# MC50_Periph.net
KiCad netlist of a schematic drawn in Altium Designer
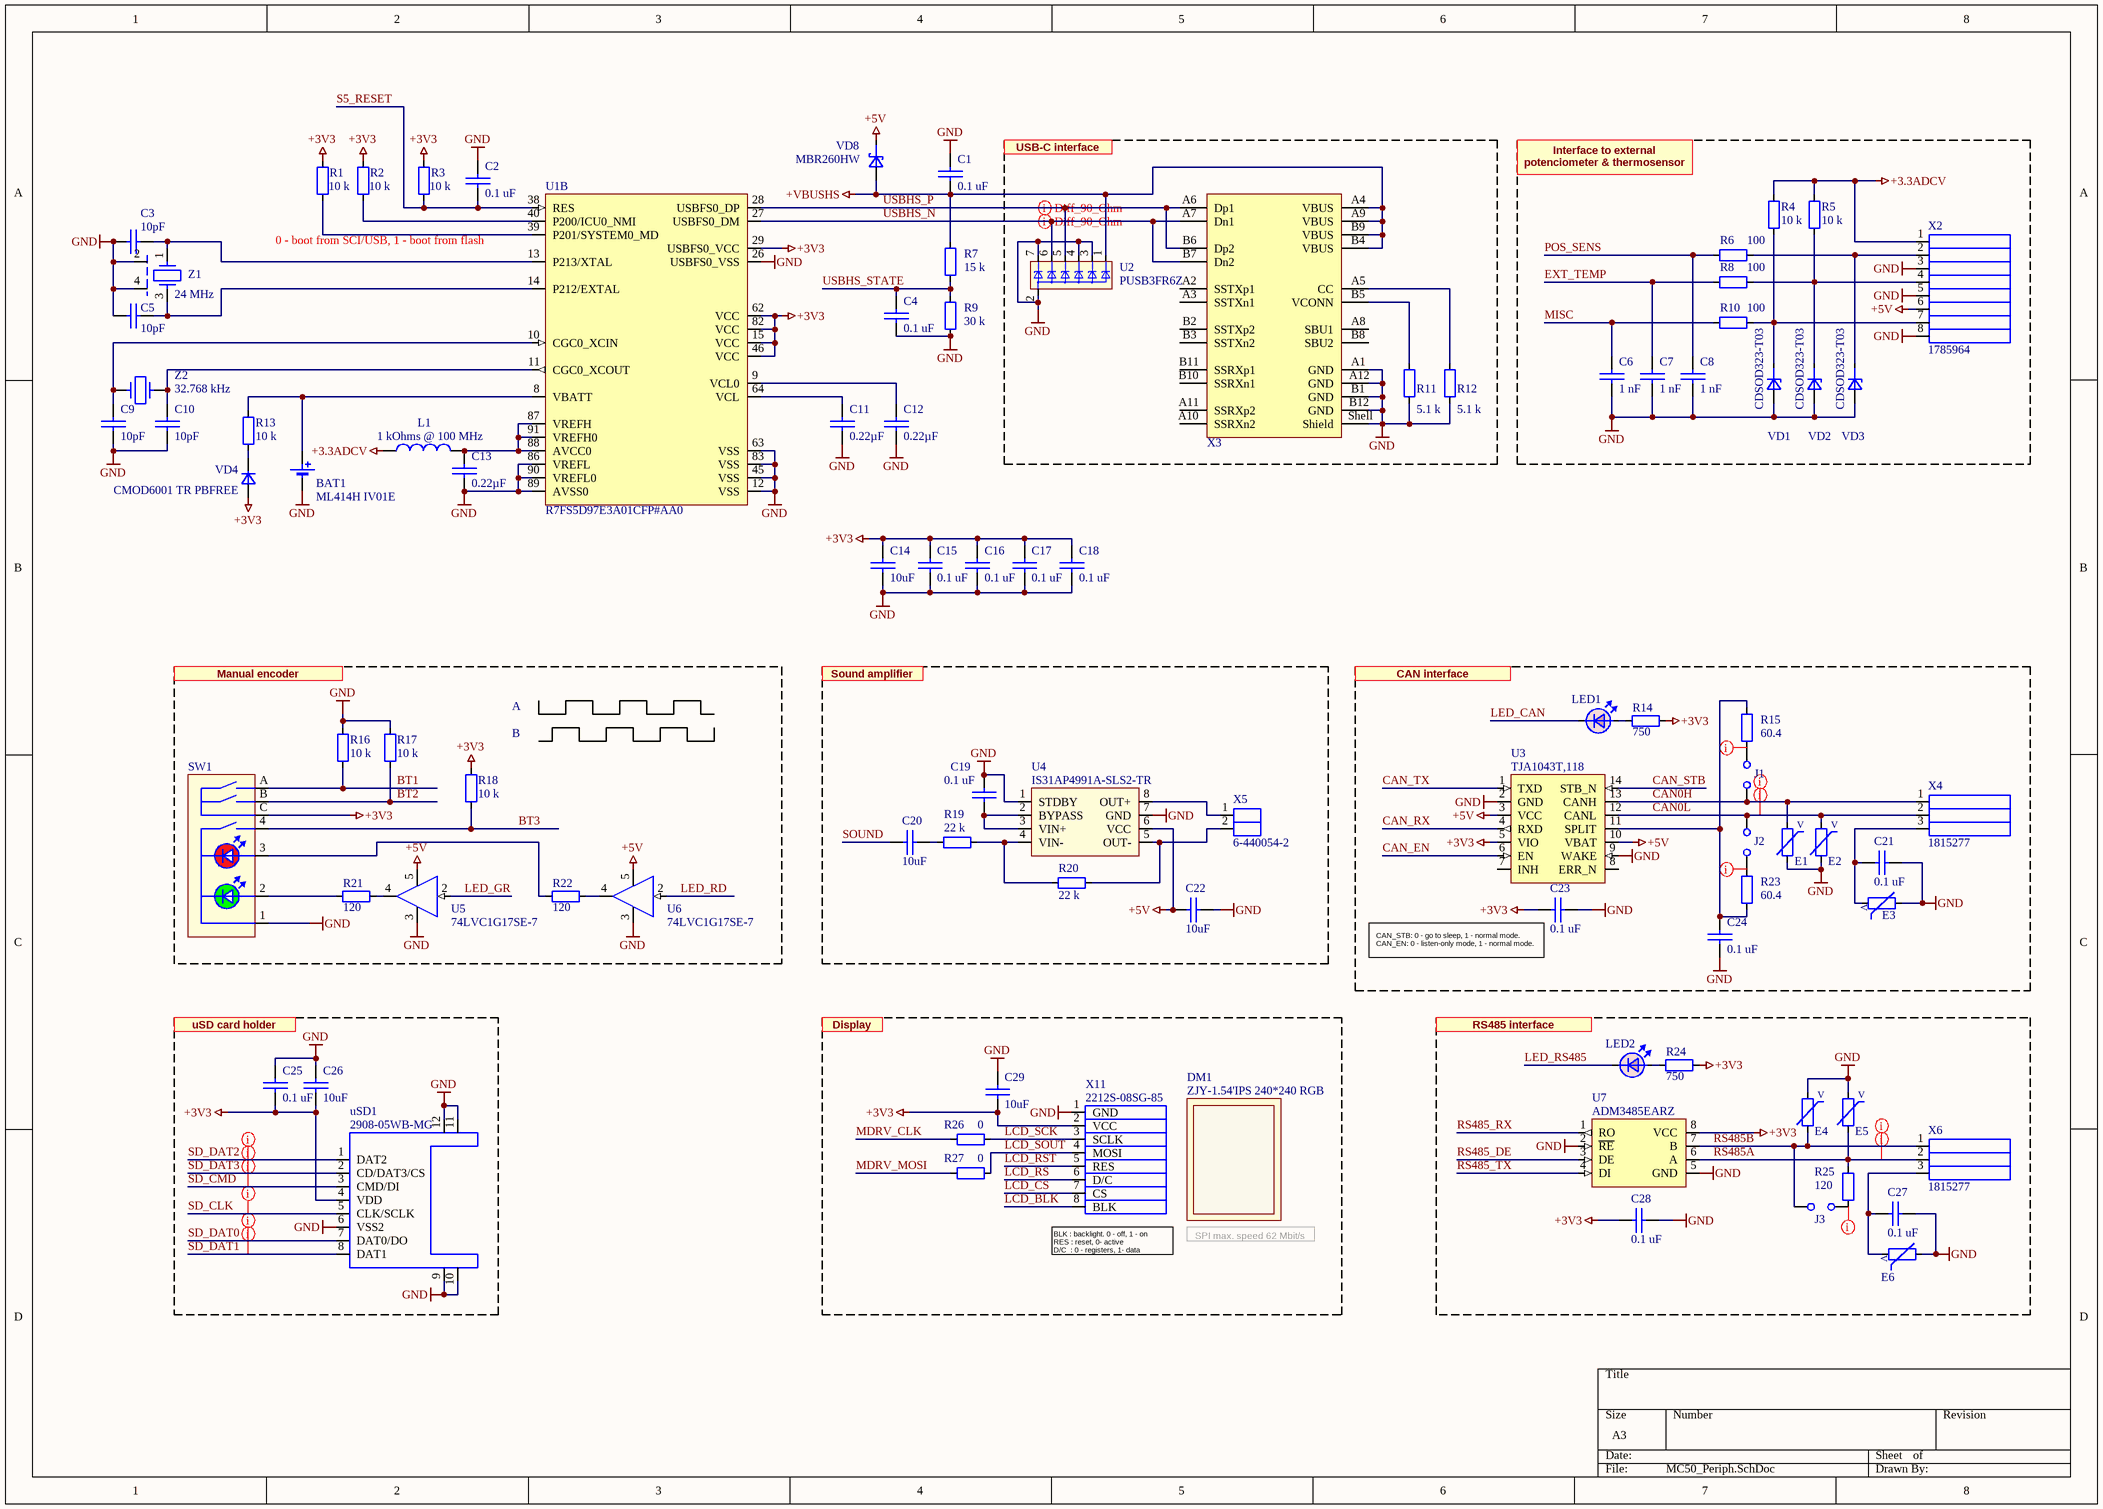
[diagram p0: MC50_Periph.SchDoc]

(export (version "E")
  (design (tool "Eeschema 10.0.6"))
  (components
    (comp (ref "BAT1")
      (value "ML414H IV01E")
      (footprint "ML414H")
      (description "Coin, 4.8mm 3V Lithium Battery Rechargeable (Secondary) 1mAh")
      (fields (field (name "PARTNUM") "728-1052-1-ND") (field (name "MANUFACTURER") "Seiko Instruments"))
      (libsource (lib "ea_PowerSources") (part "ML414H IV01E"))
    )
    (comp (ref "C1")
      (value "0.1 uF")
      (footprint "1608[0603]")
      (description "0.1 µF ±10% 50V Ceramic Capacitor X7R 0603 (1608 Metric),  \r\n-55°C ~ 125°C")
      (fields
        (field (name "TOLERANCE") "+-10%")
        (field (name "MANUFACTURER") "Walsin Technology Corporation")
      )
      (libsource (lib "ea_Capacitors_0603") (part "0603B104K500CT"))
    )
    (comp (ref "C2")
      (value "0.1 uF")
      (footprint "1608[0603]")
      (description "0.1 µF ±10% 50V Ceramic Capacitor X7R 0603 (1608 Metric),  \r\n-55°C ~ 125°C")
      (fields
        (field (name "TOLERANCE") "+-10%")
        (field (name "MANUFACTURER") "Walsin Technology Corporation")
      )
      (libsource (lib "ea_Capacitors_0603") (part "0603B104K500CT"))
    )
    (comp (ref "C3")
      (value "10pF")
      (footprint "0603 CAP")
      (description "10pF, ±5%, 50V, C0G, NP0, 0603 (1608 Metric), -55°C ~ 125°C, -, General Purpose")
      (fields
        (field (name "PART NUMBER") "CL10C100JB8NCNC")
        (field (name "MANUFACTURER") "Samsung Electro-Mechanics")
      )
      (libsource (lib "ea_PassivComps") (part "Capacitor"))
    )
    (comp (ref "C4")
      (value "0.1 uF")
      (footprint "1608[0603]")
      (description "0.1 µF ±10% 50V Ceramic Capacitor X7R 0603 (1608 Metric),  \r\n-55°C ~ 125°C")
      (fields
        (field (name "TOLERANCE") "+-10%")
        (field (name "MANUFACTURER") "Walsin Technology Corporation")
      )
      (libsource (lib "ea_Capacitors_0603") (part "0603B104K500CT"))
    )
    (comp (ref "C5")
      (value "10pF")
      (footprint "0603 CAP")
      (description "10pF, ±5%, 50V, C0G, NP0, 0603 (1608 Metric), -55°C ~ 125°C, -, General Purpose")
      (fields
        (field (name "PART NUMBER") "CL10C100JB8NCNC")
        (field (name "MANUFACTURER") "Samsung Electro-Mechanics")
      )
      (libsource (lib "ea_PassivComps") (part "Capacitor"))
    )
    (comp (ref "C6")
      (value "1 nF")
      (footprint "0603 CAP")
      (description "1000pF, ±5%, 50V, X7R, 0603 (1608 Metric), -55°C ~ 125°C, -, General Purpose")
      (fields (field (name "PART NUMBER") "CC0603JRX7R9BB102") (field (name "MANUFACTURER") "Yageo"))
      (libsource (lib "ea_PassivComps") (part "Capacitor"))
    )
    (comp (ref "C7")
      (value "1 nF")
      (footprint "0603 CAP")
      (description "1000pF, ±5%, 50V, X7R, 0603 (1608 Metric), -55°C ~ 125°C, -, General Purpose")
      (fields (field (name "PART NUMBER") "CC0603JRX7R9BB102") (field (name "MANUFACTURER") "Yageo"))
      (libsource (lib "ea_PassivComps") (part "Capacitor"))
    )
    (comp (ref "C8")
      (value "1 nF")
      (footprint "0603 CAP")
      (description "1000pF, ±5%, 50V, X7R, 0603 (1608 Metric), -55°C ~ 125°C, -, General Purpose")
      (fields (field (name "PART NUMBER") "CC0603JRX7R9BB102") (field (name "MANUFACTURER") "Yageo"))
      (libsource (lib "ea_PassivComps") (part "Capacitor"))
    )
    (comp (ref "C9")
      (value "10pF")
      (footprint "0603 CAP")
      (description "10pF, ±5%, 50V, C0G, NP0, 0603 (1608 Metric), -55°C ~ 125°C, -, General Purpose")
      (fields
        (field (name "PART NUMBER") "CL10C100JB8NCNC")
        (field (name "MANUFACTURER") "Samsung Electro-Mechanics")
      )
      (libsource (lib "ea_PassivComps") (part "Capacitor"))
    )
    (comp (ref "C10")
      (value "10pF")
      (footprint "0603 CAP")
      (description "10pF, ±5%, 50V, C0G, NP0, 0603 (1608 Metric), -55°C ~ 125°C, -, General Purpose")
      (fields
        (field (name "PART NUMBER") "CL10C100JB8NCNC")
        (field (name "MANUFACTURER") "Samsung Electro-Mechanics")
      )
      (libsource (lib "ea_PassivComps") (part "Capacitor"))
    )
    (comp (ref "C11")
      (value "0.22µF")
      (footprint "0603 CAP")
      (description "0.22µF, ±10%, 50V, X7R, 0603 (1608 Metric), -55°C ~ 125°C, -, General Purpose")
      (fields
        (field (name "PART NUMBER") "GRM188R71H224KAC4D")
        (field (name "MANUFACTURER") "Murata Electronics North America")
      )
      (libsource (lib "ea_PassivComps") (part "Capacitor"))
    )
    (comp (ref "C12")
      (value "0.22µF")
      (footprint "0603 CAP")
      (description "0.22µF, ±10%, 50V, X7R, 0603 (1608 Metric), -55°C ~ 125°C, -, General Purpose")
      (fields
        (field (name "PART NUMBER") "GRM188R71H224KAC4D")
        (field (name "MANUFACTURER") "Murata Electronics North America")
      )
      (libsource (lib "ea_PassivComps") (part "Capacitor"))
    )
    (comp (ref "C13")
      (value "0.22µF")
      (footprint "0603 CAP")
      (description "0.22µF, ±10%, 50V, X7R, 0603 (1608 Metric), -55°C ~ 125°C, -, General Purpose")
      (fields
        (field (name "PART NUMBER") "GRM188R71H224KAC4D")
        (field (name "MANUFACTURER") "Murata Electronics North America")
      )
      (libsource (lib "ea_PassivComps") (part "Capacitor"))
    )
    (comp (ref "C14")
      (value "10uF")
      (footprint "1608[0603]")
      (description "10 µF ±10% 25V Ceramic Capacitor X5R 0603 (1608 Metric), -55°C ~ 85°C")
      (fields (field (name "MANUFACTURER") "Murata Electronics") (field (name "TOLERANCE") "±10%"))
      (libsource (lib "ea_Capacitors_0603") (part "GRM188R61E106KA73D"))
    )
    (comp (ref "C15")
      (value "0.1 uF")
      (footprint "1608[0603]")
      (description "0.1 µF ±10% 50V Ceramic Capacitor X7R 0603 (1608 Metric),  \r\n-55°C ~ 125°C")
      (fields
        (field (name "TOLERANCE") "+-10%")
        (field (name "MANUFACTURER") "Walsin Technology Corporation")
      )
      (libsource (lib "ea_Capacitors_0603") (part "0603B104K500CT"))
    )
    (comp (ref "C16")
      (value "0.1 uF")
      (footprint "1608[0603]")
      (description "0.1 µF ±10% 50V Ceramic Capacitor X7R 0603 (1608 Metric),  \r\n-55°C ~ 125°C")
      (fields
        (field (name "TOLERANCE") "+-10%")
        (field (name "MANUFACTURER") "Walsin Technology Corporation")
      )
      (libsource (lib "ea_Capacitors_0603") (part "0603B104K500CT"))
    )
    (comp (ref "C17")
      (value "0.1 uF")
      (footprint "1608[0603]")
      (description "0.1 µF ±10% 50V Ceramic Capacitor X7R 0603 (1608 Metric),  \r\n-55°C ~ 125°C")
      (fields
        (field (name "TOLERANCE") "+-10%")
        (field (name "MANUFACTURER") "Walsin Technology Corporation")
      )
      (libsource (lib "ea_Capacitors_0603") (part "0603B104K500CT"))
    )
    (comp (ref "C18")
      (value "0.1 uF")
      (footprint "1608[0603]")
      (description "0.1 µF ±10% 50V Ceramic Capacitor X7R 0603 (1608 Metric),  \r\n-55°C ~ 125°C")
      (fields
        (field (name "TOLERANCE") "+-10%")
        (field (name "MANUFACTURER") "Walsin Technology Corporation")
      )
      (libsource (lib "ea_Capacitors_0603") (part "0603B104K500CT"))
    )
    (comp (ref "C19")
      (value "0.1 uF")
      (footprint "1608[0603]")
      (description "0.1 µF ±10% 50V Ceramic Capacitor X7R 0603 (1608 Metric),  \r\n-55°C ~ 125°C")
      (fields
        (field (name "TOLERANCE") "+-10%")
        (field (name "MANUFACTURER") "Walsin Technology Corporation")
      )
      (libsource (lib "ea_Capacitors_0603") (part "0603B104K500CT"))
    )
    (comp (ref "C20")
      (value "10uF")
      (footprint "1608[0603]")
      (description "10 µF ±10% 25V Ceramic Capacitor X5R 0603 (1608 Metric), -55°C ~ 85°C")
      (fields (field (name "MANUFACTURER") "Murata Electronics") (field (name "TOLERANCE") "±10%"))
      (libsource (lib "ea_Capacitors_0603") (part "GRM188R61E106KA73D"))
    )
    (comp (ref "C21")
      (value "0.1 uF")
      (footprint "1608[0603]")
      (description "0.1 µF ±10% 50V Ceramic Capacitor X7R 0603 (1608 Metric),  \r\n-55°C ~ 125°C")
      (fields
        (field (name "TOLERANCE") "+-10%")
        (field (name "MANUFACTURER") "Walsin Technology Corporation")
      )
      (libsource (lib "ea_Capacitors_0603") (part "0603B104K500CT"))
    )
    (comp (ref "C22")
      (value "10uF")
      (footprint "1608[0603]")
      (description "10 µF ±10% 25V Ceramic Capacitor X5R 0603 (1608 Metric), -55°C ~ 85°C")
      (fields (field (name "MANUFACTURER") "Murata Electronics") (field (name "TOLERANCE") "±10%"))
      (libsource (lib "ea_Capacitors_0603") (part "GRM188R61E106KA73D"))
    )
    (comp (ref "C23")
      (value "0.1 uF")
      (footprint "1608[0603]")
      (description "0.1 µF ±10% 50V Ceramic Capacitor X7R 0603 (1608 Metric),  \r\n-55°C ~ 125°C")
      (fields
        (field (name "TOLERANCE") "+-10%")
        (field (name "MANUFACTURER") "Walsin Technology Corporation")
      )
      (libsource (lib "ea_Capacitors_0603") (part "0603B104K500CT"))
    )
    (comp (ref "C24")
      (value "0.1 uF")
      (footprint "1608[0603]")
      (description "0.1 µF ±10% 50V Ceramic Capacitor X7R 0603 (1608 Metric),  \r\n-55°C ~ 125°C")
      (fields
        (field (name "TOLERANCE") "+-10%")
        (field (name "MANUFACTURER") "Walsin Technology Corporation")
      )
      (libsource (lib "ea_Capacitors_0603") (part "0603B104K500CT"))
    )
    (comp (ref "C25")
      (value "0.1 uF")
      (footprint "1608[0603]")
      (description "0.1 µF ±10% 50V Ceramic Capacitor X7R 0603 (1608 Metric),  \r\n-55°C ~ 125°C")
      (fields
        (field (name "TOLERANCE") "+-10%")
        (field (name "MANUFACTURER") "Walsin Technology Corporation")
      )
      (libsource (lib "ea_Capacitors_0603") (part "0603B104K500CT"))
    )
    (comp (ref "C26")
      (value "10uF")
      (footprint "1608[0603]")
      (description "10 µF ±10% 25V Ceramic Capacitor X5R 0603 (1608 Metric), -55°C ~ 85°C")
      (fields (field (name "MANUFACTURER") "Murata Electronics") (field (name "TOLERANCE") "±10%"))
      (libsource (lib "ea_Capacitors_0603") (part "GRM188R61E106KA73D"))
    )
    (comp (ref "C27")
      (value "0.1 uF")
      (footprint "1608[0603]")
      (description "0.1 µF ±10% 50V Ceramic Capacitor X7R 0603 (1608 Metric),  \r\n-55°C ~ 125°C")
      (fields
        (field (name "TOLERANCE") "+-10%")
        (field (name "MANUFACTURER") "Walsin Technology Corporation")
      )
      (libsource (lib "ea_Capacitors_0603") (part "0603B104K500CT"))
    )
    (comp (ref "C28")
      (value "0.1 uF")
      (footprint "1608[0603]")
      (description "0.1 µF ±10% 50V Ceramic Capacitor X7R 0603 (1608 Metric),  \r\n-55°C ~ 125°C")
      (fields
        (field (name "TOLERANCE") "+-10%")
        (field (name "MANUFACTURER") "Walsin Technology Corporation")
      )
      (libsource (lib "ea_Capacitors_0603") (part "0603B104K500CT"))
    )
    (comp (ref "C29")
      (value "10uF")
      (footprint "1608[0603]")
      (description "10 µF ±10% 25V Ceramic Capacitor X5R 0603 (1608 Metric), -55°C ~ 85°C")
      (fields (field (name "MANUFACTURER") "Murata Electronics") (field (name "TOLERANCE") "±10%"))
      (libsource (lib "ea_Capacitors_0603") (part "GRM188R61E106KA73D"))
    )
    (comp (ref "DM1")
      (value "ZJY-1.54'IPS 240*240 RGB")
      (footprint "1.54 inch IPS 240x240 w/o pins")
      (fields (field (name "PARTNUM") "ZJY-1.54'IPS 240*240(RGB)"))
      (libsource (lib "ea_LCD") (part "ZJY-1.54'IPS 240*240 RGB"))
    )
    (comp (ref "E1")
      (value "ESD03A5V5R17V")
      (footprint "0603")
      (description "Low and Ultra Low Capacitance ESD Suppressor, Voperating=5.5V, Vclamp=17V, < 1nS,1nA, 0603,")
      (fields
        (field (name "MANUFACTURER") "Stackpole Electronics Inc")
        (field (name "PARTNUM") "ESD03A5V5R17VCT-ND")
      )
      (libsource (lib "ea_TVS_protection") (part "ESD03A5V5R17V"))
    )
    (comp (ref "E2")
      (value "ESD03A5V5R17V")
      (footprint "0603")
      (description "Low and Ultra Low Capacitance ESD Suppressor, Voperating=5.5V, Vclamp=17V, < 1nS,1nA, 0603,")
      (fields
        (field (name "MANUFACTURER") "Stackpole Electronics Inc")
        (field (name "PARTNUM") "ESD03A5V5R17VCT-ND")
      )
      (libsource (lib "ea_TVS_protection") (part "ESD03A5V5R17V"))
    )
    (comp (ref "E3")
      (value "ESD03A5V5R17V")
      (footprint "0603")
      (description "Low and Ultra Low Capacitance ESD Suppressor, Voperating=5.5V, Vclamp=17V, < 1nS,1nA, 0603,")
      (fields
        (field (name "MANUFACTURER") "Stackpole Electronics Inc")
        (field (name "PARTNUM") "ESD03A5V5R17VCT-ND")
      )
      (libsource (lib "") (part "ESD03A5V5R17V_1"))
    )
    (comp (ref "E4")
      (value "ESD03A5V5R17V")
      (footprint "0603")
      (description "Low and Ultra Low Capacitance ESD Suppressor, Voperating=5.5V, Vclamp=17V, < 1nS,1nA, 0603,")
      (fields
        (field (name "MANUFACTURER") "Stackpole Electronics Inc")
        (field (name "PARTNUM") "ESD03A5V5R17VCT-ND")
      )
      (libsource (lib "ea_TVS_protection") (part "ESD03A5V5R17V"))
    )
    (comp (ref "E5")
      (value "ESD03A5V5R17V")
      (footprint "0603")
      (description "Low and Ultra Low Capacitance ESD Suppressor, Voperating=5.5V, Vclamp=17V, < 1nS,1nA, 0603,")
      (fields
        (field (name "MANUFACTURER") "Stackpole Electronics Inc")
        (field (name "PARTNUM") "ESD03A5V5R17VCT-ND")
      )
      (libsource (lib "ea_TVS_protection") (part "ESD03A5V5R17V"))
    )
    (comp (ref "E6")
      (value "823 560 505 60")
      (footprint "0603")
      (description "Low and Ultra Low Capacitance ESD Suppressor, Voperating=5.5V, Vclamp=17V, < 1nS,1nA, 0603,")
      (fields
        (field (name "MANUFACTURER") "Stackpole Electronics Inc")
        (field (name "PARTNUM") "ESD03A5V5R17VCT-ND")
      )
      (libsource (lib "") (part "ESD03A5V5R17V_1"))
    )
    (comp (ref "J1")
      (value "2PH1-02-UA")
      (footprint "2PH1-02-UA")
      (description "Connector Header Through Hole 2 position 0.079\" (2.00mm)")
      (fields (field (name "MANUFACTURER") "Adam Tech") (field (name "PARTNUM") "2057-2PH1-02-UA-ND"))
      (libsource (lib "ea_Commutation") (part "2PH1-02-UA"))
    )
    (comp (ref "J2")
      (value "2PH1-02-UA")
      (footprint "2PH1-02-UA")
      (description "Connector Header Through Hole 2 position 0.079\" (2.00mm)")
      (fields (field (name "MANUFACTURER") "Adam Tech") (field (name "PARTNUM") "2057-2PH1-02-UA-ND"))
      (libsource (lib "ea_Commutation") (part "2PH1-02-UA"))
    )
    (comp (ref "J3")
      (value "2PH1-02-UA")
      (footprint "2PH1-02-UA")
      (description "Connector Header Through Hole 2 position 0.079\" (2.00mm)")
      (fields (field (name "MANUFACTURER") "Adam Tech") (field (name "PARTNUM") "2057-2PH1-02-UA-ND"))
      (libsource (lib "ea_Commutation") (part "2PH1-02-UA"))
    )
    (comp (ref "L1")
      (value "1 kOhms @ 100 MHz")
      (footprint "0603")
      (description "1 kOhms @ 100 MHz 1 Power, Signal Line Ferrite Bead 0603 (1608 Metric) 200mA 600mOhm")
      (fields
        (field (name "MANUFACTURER") "Laird-Signal Integrity Products")
        (field (name "PARTNUM") "240-2378-1-ND")
      )
      (libsource (lib "ea_Inductors") (part "HZ0603B102R-10"))
    )
    (comp (ref "LED1")
      (value "SML-211UTT86")
      (footprint "0805 LED")
      (description "0805 red LED, hibright, 2 mA, 1.8V, 130°")
      (fields (field (name "MANUFACTURER") "Rohm") (field (name "PARTNUM") "511-1292-1-ND"))
      (libsource (lib "ea_Indicators") (part "SML-211UTT86"))
    )
    (comp (ref "LED2")
      (value "SML-211UTT86")
      (footprint "0805 LED")
      (description "0805 red LED, hibright, 2 mA, 1.8V, 130°")
      (fields (field (name "MANUFACTURER") "Rohm") (field (name "PARTNUM") "511-1292-1-ND"))
      (libsource (lib "ea_Indicators") (part "SML-211UTT86"))
    )
    (comp (ref "R1")
      (value "10 k")
      (footprint "0603")
      (fields
        (field (name "MANUFACTURER") "Bourns Inc.")
        (field (name "TOLERANCE") "±1%")
        (field (name "VOLTAGE") "75V")
      )
      (libsource (lib "") (part "Resistor_1"))
    )
    (comp (ref "R2")
      (value "10 k")
      (footprint "0603")
      (fields
        (field (name "MANUFACTURER") "Bourns Inc.")
        (field (name "TOLERANCE") "±1%")
        (field (name "VOLTAGE") "75V")
      )
      (libsource (lib "") (part "Resistor_1"))
    )
    (comp (ref "R3")
      (value "10 k")
      (footprint "0603")
      (fields
        (field (name "MANUFACTURER") "Bourns Inc.")
        (field (name "TOLERANCE") "±1%")
        (field (name "VOLTAGE") "75V")
      )
      (libsource (lib "") (part "Resistor_1"))
    )
    (comp (ref "R4")
      (value "10 k")
      (footprint "0603")
      (fields
        (field (name "MANUFACTURER") "Bourns Inc.")
        (field (name "TOLERANCE") "±1%")
        (field (name "VOLTAGE") "75V")
      )
      (libsource (lib "") (part "Resistor_1"))
    )
    (comp (ref "R5")
      (value "10 k")
      (footprint "0603")
      (fields
        (field (name "MANUFACTURER") "Bourns Inc.")
        (field (name "TOLERANCE") "±1%")
        (field (name "VOLTAGE") "75V")
      )
      (libsource (lib "") (part "Resistor_1"))
    )
    (comp (ref "R6")
      (value "100")
      (footprint "0603")
      (fields
        (field (name "MANUFACTURER") "Stackpole Electronics Inc.")
        (field (name "TOLERANCE") "±1%")
        (field (name "VOLTAGE") "75V")
      )
      (libsource (lib "") (part "Resistor_2"))
    )
    (comp (ref "R7")
      (value "15 k")
      (footprint "0603")
      (fields
        (field (name "MANUFACTURER") "Stackpole Electronics Inc.")
        (field (name "TOLERANCE") "±1%")
        (field (name "VOLTAGE") "75V")
      )
      (libsource (lib "") (part "Resistor_1"))
    )
    (comp (ref "R8")
      (value "100")
      (footprint "0603")
      (fields
        (field (name "MANUFACTURER") "Stackpole Electronics Inc.")
        (field (name "TOLERANCE") "±1%")
        (field (name "VOLTAGE") "75V")
      )
      (libsource (lib "") (part "Resistor_2"))
    )
    (comp (ref "R9")
      (value "30 k")
      (footprint "0603")
      (fields
        (field (name "MANUFACTURER") "Stackpole Electronics Inc.")
        (field (name "TOLERANCE") "±1%")
        (field (name "VOLTAGE") "75V")
      )
      (libsource (lib "") (part "Resistor_1"))
    )
    (comp (ref "R10")
      (value "100")
      (footprint "0603")
      (fields
        (field (name "MANUFACTURER") "Stackpole Electronics Inc.")
        (field (name "TOLERANCE") "±1%")
        (field (name "VOLTAGE") "75V")
      )
      (libsource (lib "") (part "Resistor_2"))
    )
    (comp (ref "R11")
      (value "5.1 k")
      (footprint "0603")
      (fields
        (field (name "MANUFACTURER") "Stackpole Electronics Inc.")
        (field (name "TOLERANCE") "±1%")
        (field (name "VOLTAGE") "75V")
      )
      (libsource (lib "") (part "Resistor_1"))
    )
    (comp (ref "R12")
      (value "5.1 k")
      (footprint "0603")
      (fields
        (field (name "MANUFACTURER") "Stackpole Electronics Inc.")
        (field (name "TOLERANCE") "±1%")
        (field (name "VOLTAGE") "75V")
      )
      (libsource (lib "") (part "Resistor_1"))
    )
    (comp (ref "R13")
      (value "10 k")
      (footprint "0603")
      (fields
        (field (name "MANUFACTURER") "Bourns Inc.")
        (field (name "TOLERANCE") "±1%")
        (field (name "VOLTAGE") "75V")
      )
      (libsource (lib "") (part "Resistor_1"))
    )
    (comp (ref "R14")
      (value "750")
      (footprint "0603")
      (fields
        (field (name "MANUFACTURER") "Stackpole Electronics Inc.")
        (field (name "TOLERANCE") "±1%")
        (field (name "VOLTAGE") "75V")
      )
      (libsource (lib "ea_PassivComps") (part "Resistor"))
    )
    (comp (ref "R15")
      (value "60.4")
      (footprint "0603")
      (fields
        (field (name "MANUFACTURER") "Vishay Dale")
        (field (name "TOLERANCE") "±1%")
        (field (name "VOLTAGE") "75V")
      )
      (libsource (lib "") (part "Resistor_1"))
    )
    (comp (ref "R16")
      (value "10 k")
      (footprint "0603")
      (fields
        (field (name "MANUFACTURER") "Bourns Inc.")
        (field (name "TOLERANCE") "±1%")
        (field (name "VOLTAGE") "75V")
      )
      (libsource (lib "") (part "Resistor_1"))
    )
    (comp (ref "R17")
      (value "10 k")
      (footprint "0603")
      (fields
        (field (name "MANUFACTURER") "Bourns Inc.")
        (field (name "TOLERANCE") "±1%")
        (field (name "VOLTAGE") "75V")
      )
      (libsource (lib "") (part "Resistor_1"))
    )
    (comp (ref "R18")
      (value "10 k")
      (footprint "0603")
      (fields
        (field (name "MANUFACTURER") "Bourns Inc.")
        (field (name "TOLERANCE") "±1%")
        (field (name "VOLTAGE") "75V")
      )
      (libsource (lib "") (part "Resistor_1"))
    )
    (comp (ref "R19")
      (value "22 k")
      (footprint "0603")
      (fields
        (field (name "MANUFACTURER") "Stackpole Electronics Inc.")
        (field (name "TOLERANCE") "±1%")
        (field (name "VOLTAGE") "75V")
      )
      (libsource (lib "ea_PassivComps") (part "Resistor"))
    )
    (comp (ref "R20")
      (value "22 k")
      (footprint "0603")
      (fields
        (field (name "MANUFACTURER") "Stackpole Electronics Inc.")
        (field (name "TOLERANCE") "±1%")
        (field (name "VOLTAGE") "75V")
      )
      (libsource (lib "ea_PassivComps") (part "Resistor"))
    )
    (comp (ref "R21")
      (value "120")
      (footprint "0603")
      (fields
        (field (name "MANUFACTURER") "Stackpole Electronics Inc.")
        (field (name "TOLERANCE") "±1%")
        (field (name "VOLTAGE") "75V")
      )
      (libsource (lib "") (part "Resistor_2"))
    )
    (comp (ref "R22")
      (value "120")
      (footprint "0603")
      (fields
        (field (name "MANUFACTURER") "Stackpole Electronics Inc.")
        (field (name "TOLERANCE") "±1%")
        (field (name "VOLTAGE") "75V")
      )
      (libsource (lib "") (part "Resistor_2"))
    )
    (comp (ref "R23")
      (value "60.4")
      (footprint "0603")
      (fields
        (field (name "MANUFACTURER") "Vishay Dale")
        (field (name "TOLERANCE") "±1%")
        (field (name "VOLTAGE") "75V")
      )
      (libsource (lib "") (part "Resistor_1"))
    )
    (comp (ref "R24")
      (value "750")
      (footprint "0603")
      (fields
        (field (name "MANUFACTURER") "Stackpole Electronics Inc.")
        (field (name "TOLERANCE") "±1%")
        (field (name "VOLTAGE") "75V")
      )
      (libsource (lib "ea_PassivComps") (part "Resistor"))
    )
    (comp (ref "R25")
      (value "120")
      (footprint "0603")
      (fields
        (field (name "MANUFACTURER") "Stackpole Electronics Inc.")
        (field (name "TOLERANCE") "±1%")
        (field (name "VOLTAGE") "75V")
      )
      (libsource (lib "") (part "Resistor_1"))
    )
    (comp (ref "R26")
      (value "0")
      (footprint "0603")
      (description "0 Ohms, 0.1W, 1/10W, Thick Film, 0603 (1608 Metric), -55°C ~ 155°C, Automotive AEC-Q200")
      (fields
        (field (name "MANUFACTURER") "Stackpole Electronics Inc.")
        (field (name "PARTNUM") "RMCF0603ZT0R00CT-ND")
      )
      (libsource (lib "ea_PassivComps") (part "Resistor"))
    )
    (comp (ref "R27")
      (value "0")
      (footprint "0603")
      (description "0 Ohms, 0.1W, 1/10W, Thick Film, 0603 (1608 Metric), -55°C ~ 155°C, Automotive AEC-Q200")
      (fields
        (field (name "MANUFACTURER") "Stackpole Electronics Inc.")
        (field (name "PARTNUM") "RMCF0603ZT0R00CT-ND")
      )
      (libsource (lib "") (part "Resistor_2"))
    )
    (comp (ref "SW1")
      (value "PEL12D-4225S-S2024")
      (footprint "PEL12D-4225S-S2024")
      (description "Rotary Encoder Mechanical 24 Quadrature (Incremental) Vertical")
      (fields (field (name "MANUFACTURER") "Bourns Inc.") (field (name "PARTNUM") "PEL12D-4225S-S2024-ND"))
      (libsource (lib "ea_Commutation") (part "PEL12D-4225S-S2024"))
    )
    (comp (ref "U1")
      (value "R7FS5D97E3A01CFP#AA0")
      (footprint "P-LFQFP100-14x14-0.50")
      (fields (field (name "MANUFACTURER") "Renesas") (field (name "PARTNUM") "968-S5D97E3A01CFPAA0"))
      (libsource (lib "ea_IC_CPU") (part "R7FS5D97E3A01CFP#AA0"))
    )
    (comp (ref "U2")
      (value "PUSB3FR6Z")
      (footprint "SOT1358-1")
      (description "TVS Diode, 3V (Typ) Clamp 5A (8/20µs) Ipp ,  7-XSON (1.1x2.1), -40°C ~ 85°C (TA)")
      (fields (field (name "MANUFACTURER") "Nexperia USA Inc.") (field (name "PARTNUM") "1727-2027-1-ND"))
      (libsource (lib "ea_TVS_protection") (part "PUSB3FR6Z"))
    )
    (comp (ref "U3")
      (value "TJA1043T,118")
      (footprint "SOT108-1")
      (description "1/1 Transceiver Half CANbus, 5Mbps, 4.5-5.5V, 3V IO,  14-SO, -40°C ~ 150°C")
      (fields (field (name "MANUFACTURER") "NXP") (field (name "PARTNUM") "2776120RL"))
      (libsource (lib "ea_IC_Interfaces") (part "TJA1043T,118"))
    )
    (comp (ref "U4")
      (value "IS31AP4991A-SLS2-TR")
      (footprint "MSOP-8")
      (description "Amplifier IC 1-Channel (Mono) Class AB, 2.7V ~ 5.5V,  1.15W x 1 @ 8Ohm, 8-MSOP, -40°C ~ 85°C (TA)")
      (fields
        (field (name "MANUFACTURER") "Lumissil Microsystems")
        (field (name "PARTNUM") "2521-IS31AP4991A-SLS2-TRCT-ND")
      )
      (libsource (lib "ea_IC_audio") (part "IS31AP4991A-SLS2-TR"))
    )
    (comp (ref "U5")
      (value "74LVC1G17SE-7")
      (footprint "SOT-353 ON Semi")
      (description "IC SGL SCHMITT BUFFER SOT353")
      (fields
        (field (name "MANUFACTURER") "Diodes Incorporated")
        (field (name "PARTNUM") "74LVC1G17SE-7CT-ND")
      )
      (libsource (lib "ea_IC_Logic") (part "74LVC1G17SE-7"))
    )
    (comp (ref "U6")
      (value "74LVC1G17SE-7")
      (footprint "SOT-353 ON Semi")
      (description "IC SGL SCHMITT BUFFER SOT353")
      (fields
        (field (name "MANUFACTURER") "Diodes Incorporated")
        (field (name "PARTNUM") "74LVC1G17SE-7CT-ND")
      )
      (libsource (lib "ea_IC_Logic") (part "74LVC1G17SE-7"))
    )
    (comp (ref "U7")
      (value "ADM3485EARZ")
      (footprint "SO-8")
      (description "1/1 Transceiver Half RS422, RS485, VCC 3.3 V,  8-SOIC, -40°C ~ 85°C")
      (fields (field (name "MANUFACTURER") "Analog Devices") (field (name "PARTNUM") "584-ADM3485EARZ-R7"))
      (libsource (lib "ea_IC_Interfaces") (part "ADM3485EARZ"))
    )
    (comp (ref "uSD1")
      (value "2908-05WB-MG")
      (footprint "2908-05WB-MG")
      (description "microSD cadr holder")
      (fields (field (name "MANUFACTURER") "3M"))
      (libsource (lib "ea_CARD_holders") (part "2908-05WB-MG"))
    )
    (comp (ref "VD1")
      (value "CDSOD323-T03")
      (footprint "SOD323")
      (description "TVS 350W, 3.3V, Vbrk=4V, -55..150C, SC-76, SOD-323")
      (fields (field (name "MANUFACTURER") "Bourns Inc.") (field (name "PARTNUM") "CDSOD323-T03CT-ND"))
      (libsource (lib "ea_TVS_protection") (part "CDSOD323-T03"))
    )
    (comp (ref "VD2")
      (value "CDSOD323-T03")
      (footprint "SOD323")
      (description "TVS 350W, 3.3V, Vbrk=4V, -55..150C, SC-76, SOD-323")
      (fields (field (name "MANUFACTURER") "Bourns Inc.") (field (name "PARTNUM") "CDSOD323-T03CT-ND"))
      (libsource (lib "ea_TVS_protection") (part "CDSOD323-T03"))
    )
    (comp (ref "VD3")
      (value "CDSOD323-T03")
      (footprint "SOD323")
      (description "TVS 350W, 3.3V, Vbrk=4V, -55..150C, SC-76, SOD-323")
      (fields (field (name "MANUFACTURER") "Bourns Inc.") (field (name "PARTNUM") "CDSOD323-T03CT-ND"))
      (libsource (lib "ea_TVS_protection") (part "CDSOD323-T03"))
    )
    (comp (ref "VD4")
      (value "CMOD6001 TR PBFREE")
      (footprint "SOD523")
      (description "Diode Standard 85V 100mA, 005nA @ 75V, SOD-523, -65°C ~ 150°C")
      (fields
        (field (name "MANUFACTURER") "Central Semiconductor Corp")
        (field (name "PARTNUM") "1514-CMOD6001TRPBFREECT-ND")
      )
      (libsource (lib "ea_Diodes") (part "BAV116T-7"))
    )
    (comp (ref "VD8")
      (value "MBR260HW")
      (footprint "SOD-123")
      (description "Diode Schottky  60V, 2A, 660mV @ 2A, -, SOD-123, -55°C ~ 150°C")
      (fields
        (field (name "PARTNAME") "MBR260HW")
        (field (name "PART NUMBER") "APD240KDTR-G1")
        (field (name "MANUFACTURER") "Diodes Incorporated")
      )
      (libsource (lib "ea_ActiveComps") (part "Schottky"))
    )
    (comp (ref "X2")
      (value "1785964")
      (footprint "1785964")
      (fields (field (name "MANUFACTURER") "Phoenix Contact"))
      (libsource (lib "ea_Connectors_2.5_mm_pitch") (part "1785964"))
    )
    (comp (ref "X3")
      (value "632722110112")
      (footprint "632722110112")
      (description "WR-USB 3.1 Type C, Receptacle, Vertical, SMT")
      (fields (field (name "MANUFACTURER") "Wurth Elektronik"))
      (libsource (lib "WR-USB") (part "632722110112"))
    )
    (comp (ref "X4")
      (value "1815277")
      (footprint "1815277")
      (fields (field (name "MANUFACTURER") "Phoenix Contact"))
      (libsource (lib "ea_Connectors_2.5_mm_pitch") (part "1815277"))
    )
    (comp (ref "X5")
      (value "6-440054-2")
      (footprint "6-440054-2")
      (description "Connector Header Through Hole, Right Angle 2 position 0.079\" (2.00mm)")
      (fields
        (field (name "MANUFACTURER") "TE Connectivity AMP Connectors")
        (field (name "PARTNUM") "A128968-ND")
      )
      (libsource (lib "ea_Connectors_2.0_mm_pitch") (part "6-440054-2"))
    )
    (comp (ref "X6")
      (value "1815277")
      (footprint "1815277")
      (fields (field (name "MANUFACTURER") "Phoenix Contact"))
      (libsource (lib "ea_Connectors_2.5_mm_pitch") (part "1815277"))
    )
    (comp (ref "X11")
      (value "2212S-08SG-85")
      (footprint "2212S-08SG-85")
      (description "PCB Receptacle, Board-to-Board, 2.54 mm, 1 Rows, 8 Contacts, Through Hole Mount, 2212S")
      (fields (field (name "MANUFACTURER") "MULTICOMP PRO") (field (name "PARTNUM") "1593463"))
      (libsource (lib "ea_Connectors_pin_headers") (part "2212S-08SG-85"))
    )
    (comp (ref "Z1")
      (value "24 MHz")
      (footprint "4-SMD 2.00mm x 1.60mm")
      (description "24 MHz, 10 pF, ±20ppm, 2.00mm x 1.60mm, -40°C ~ 85°C")
      (fields (field (name "MANUFACTURER") "Abracon LLC") (field (name "PARTNUM") "535-10940-1-ND"))
      (libsource (lib "ea_OSC_CLK_GEN") (part "ABM11-24.000MHZ-D2X-T3"))
    )
    (comp (ref "Z2")
      (value "32.768 kHz")
      (footprint "ABS7")
      (description "32.768 kHz, 12.5 pF, 70 kOhm, ±20ppm, 3.2 x 1.5 mm, -40°C ~ 85°C")
      (fields (field (name "MANUFACTURER") "Abracon Corporation") (field (name "PARTNUM") "535-9542-1-ND"))
      (libsource (lib "ea_OSC_CLK_GEN") (part "ABS07-32.768KHZ-T"))
    )
  )
  (nets
    (net (code "1") (name "+3.3ADCV") (class "Default")
      (node (ref "L1") (pin "1") (pinfunction "1_1") (pintype "passive"))
      (node (ref "R4") (pin "2") (pinfunction "2_2") (pintype "passive"))
      (node (ref "R5") (pin "2") (pinfunction "2_2") (pintype "passive"))
      (node (ref "X2") (pin "1") (pinfunction "1_1") (pintype "passive"))
    )
    (net (code "2") (name "+3V3") (class "Default")
      (node (ref "C14") (pin "1") (pinfunction "1_1") (pintype "passive"))
      (node (ref "C15") (pin "2") (pinfunction "2_2") (pintype "passive"))
      (node (ref "C16") (pin "2") (pinfunction "2_2") (pintype "passive"))
      (node (ref "C17") (pin "2") (pinfunction "2_2") (pintype "passive"))
      (node (ref "C18") (pin "2") (pinfunction "2_2") (pintype "passive"))
      (node (ref "C23") (pin "2") (pinfunction "2_2") (pintype "passive"))
      (node (ref "C25") (pin "1") (pinfunction "1_1") (pintype "passive"))
      (node (ref "C26") (pin "2") (pinfunction "2_2") (pintype "passive"))
      (node (ref "C28") (pin "2") (pinfunction "2_2") (pintype "passive"))
      (node (ref "C29") (pin "2") (pinfunction "2_2") (pintype "passive"))
      (node (ref "R1") (pin "2") (pinfunction "2_2") (pintype "passive"))
      (node (ref "R14") (pin "2") (pinfunction "2_2") (pintype "passive"))
      (node (ref "R18") (pin "2") (pinfunction "2_2") (pintype "passive"))
      (node (ref "R2") (pin "2") (pinfunction "2_2") (pintype "passive"))
      (node (ref "R24") (pin "2") (pinfunction "2_2") (pintype "passive"))
      (node (ref "R3") (pin "2") (pinfunction "2_2") (pintype "passive"))
      (node (ref "SW1") (pin "C") (pinfunction "C_C") (pintype "passive"))
      (node (ref "U1") (pin "15") (pinfunction "VCC_15") (pintype "power_in"))
      (node (ref "U1") (pin "29") (pinfunction "USBFS0_VCC_29") (pintype "power_in"))
      (node (ref "U1") (pin "46") (pinfunction "VCC_46") (pintype "power_in"))
      (node (ref "U1") (pin "62") (pinfunction "VCC_62") (pintype "power_in"))
      (node (ref "U1") (pin "82") (pinfunction "VCC_82") (pintype "power_in"))
      (node (ref "U3") (pin "5") (pinfunction "VIO_5") (pintype "power_in"))
      (node (ref "U7") (pin "8") (pinfunction "VCC_8") (pintype "power_in"))
      (node (ref "VD4") (pin "2") (pinfunction "A_2") (pintype "passive"))
      (node (ref "X11") (pin "2") (pinfunction "VCC_2") (pintype "passive"))
      (node (ref "uSD1") (pin "4") (pinfunction "VDD_4") (pintype "passive"))
    )
    (net (code "3") (name "+5V") (class "Default")
      (node (ref "C22") (pin "1") (pinfunction "1_1") (pintype "passive"))
      (node (ref "U3") (pin "10") (pinfunction "VBAT_10") (pintype "power_in"))
      (node (ref "U3") (pin "3") (pinfunction "VCC_3") (pintype "power_in"))
      (node (ref "U4") (pin "6") (pinfunction "VCC_6") (pintype "passive"))
      (node (ref "U5") (pin "5") (pinfunction "VCC_5") (pintype "power_in"))
      (node (ref "U6") (pin "5") (pinfunction "VCC_5") (pintype "power_in"))
      (node (ref "VD8") (pin "1") (pinfunction "C_1") (pintype "passive"))
      (node (ref "X2") (pin "6") (pinfunction "6_6") (pintype "passive"))
    )
    (net (code "4") (name "+VBUSHS") (class "Default")
      (node (ref "C1") (pin "1") (pinfunction "1_1") (pintype "passive"))
      (node (ref "R7") (pin "2") (pinfunction "2_2") (pintype "passive"))
      (node (ref "U2") (pin "1") (pinfunction "1_1") (pintype "passive"))
      (node (ref "VD8") (pin "2") (pinfunction "A_2") (pintype "passive"))
      (node (ref "X3") (pin "A4") (pinfunction "VBUS_A4") (pintype "passive"))
      (node (ref "X3") (pin "A9") (pinfunction "VBUS_A9") (pintype "passive"))
      (node (ref "X3") (pin "B4") (pinfunction "VBUS_B4") (pintype "passive"))
      (node (ref "X3") (pin "B9") (pinfunction "VBUS_B9") (pintype "passive"))
    )
    (net (code "5") (name "/BT1") (class "Default")
      (node (ref "R16") (pin "1") (pinfunction "1_1") (pintype "passive"))
      (node (ref "SW1") (pin "A") (pinfunction "A_A") (pintype "passive"))
    )
    (net (code "6") (name "/BT2") (class "Default")
      (node (ref "R17") (pin "1") (pinfunction "1_1") (pintype "passive"))
      (node (ref "SW1") (pin "B") (pinfunction "B_B") (pintype "passive"))
    )
    (net (code "7") (name "/BT3") (class "Default")
      (node (ref "R18") (pin "1") (pinfunction "1_1") (pintype "passive"))
      (node (ref "SW1") (pin "4") (pinfunction "4_4") (pintype "passive"))
    )
    (net (code "8") (name "/CAN0H") (class "Default")
      (node (ref "E1") (pin "2") (pinfunction "2_2") (pintype "passive"))
      (node (ref "J1") (pin "1") (pinfunction "1_1") (pintype "passive"))
      (node (ref "U3") (pin "13") (pinfunction "CANH_13") (pintype "bidirectional"))
      (node (ref "X4") (pin "1") (pinfunction "1_1") (pintype "passive"))
    )
    (net (code "9") (name "/CAN0L") (class "Default")
      (node (ref "E2") (pin "2") (pinfunction "2_2") (pintype "passive"))
      (node (ref "J2") (pin "2") (pinfunction "2_2") (pintype "passive"))
      (node (ref "U3") (pin "12") (pinfunction "CANL_12") (pintype "bidirectional"))
      (node (ref "X4") (pin "2") (pinfunction "2_2") (pintype "passive"))
    )
    (net (code "10") (name "/CAN_EN") (class "Default")
      (node (ref "U3") (pin "6") (pinfunction "EN_6") (pintype "input"))
    )
    (net (code "11") (name "/CAN_RX") (class "Default")
      (node (ref "U3") (pin "4") (pinfunction "RXD_4") (pintype "output"))
    )
    (net (code "12") (name "/CAN_STB") (class "Default")
      (node (ref "U3") (pin "14") (pinfunction "STB_N_14") (pintype "input"))
    )
    (net (code "13") (name "/CAN_TX") (class "Default")
      (node (ref "U3") (pin "1") (pinfunction "TXD_1") (pintype "input"))
    )
    (net (code "14") (name "/EXT_TEMP") (class "Default")
      (node (ref "C7") (pin "1") (pinfunction "1_1") (pintype "passive"))
      (node (ref "R8") (pin "2") (pinfunction "2_2") (pintype "passive"))
    )
    (net (code "15") (name "/LCD_BLK") (class "Default")
      (node (ref "X11") (pin "8") (pinfunction "BLK_8") (pintype "passive"))
    )
    (net (code "16") (name "/LCD_CS") (class "Default")
      (node (ref "X11") (pin "7") (pinfunction "CS_7") (pintype "passive"))
    )
    (net (code "17") (name "/LCD_RS") (class "Default")
      (node (ref "X11") (pin "6") (pinfunction "D/C_6") (pintype "passive"))
    )
    (net (code "18") (name "/LCD_RST") (class "Default")
      (node (ref "X11") (pin "5") (pinfunction "RES_5") (pintype "passive"))
    )
    (net (code "19") (name "/LCD_SCK") (class "Default")
      (node (ref "R26") (pin "2") (pinfunction "2_2") (pintype "passive"))
      (node (ref "X11") (pin "3") (pinfunction "SCLK_3") (pintype "passive"))
    )
    (net (code "20") (name "/LCD_SOUT") (class "Default")
      (node (ref "R27") (pin "1") (pinfunction "1_1") (pintype "passive"))
      (node (ref "X11") (pin "4") (pinfunction "MOSI_4") (pintype "passive"))
    )
    (net (code "21") (name "/LED_CAN") (class "Default")
      (node (ref "LED1") (pin "2") (pinfunction "2_2") (pintype "passive"))
    )
    (net (code "22") (name "/LED_GR") (class "Default")
      (node (ref "U5") (pin "2") (pinfunction "A_2") (pintype "input"))
    )
    (net (code "23") (name "/LED_RD") (class "Default")
      (node (ref "U6") (pin "2") (pinfunction "A_2") (pintype "input"))
    )
    (net (code "24") (name "/LED_RS485") (class "Default")
      (node (ref "LED2") (pin "2") (pinfunction "2_2") (pintype "passive"))
    )
    (net (code "25") (name "/MDRV_CLK") (class "Default")
      (node (ref "R26") (pin "1") (pinfunction "1_1") (pintype "passive"))
    )
    (net (code "26") (name "/MDRV_MOSI") (class "Default")
      (node (ref "R27") (pin "2") (pinfunction "2_2") (pintype "passive"))
    )
    (net (code "27") (name "/MISC") (class "Default")
      (node (ref "C6") (pin "1") (pinfunction "1_1") (pintype "passive"))
      (node (ref "R10") (pin "2") (pinfunction "2_2") (pintype "passive"))
    )
    (net (code "28") (name "/POS_SENS") (class "Default")
      (node (ref "C8") (pin "1") (pinfunction "1_1") (pintype "passive"))
      (node (ref "R6") (pin "2") (pinfunction "2_2") (pintype "passive"))
    )
    (net (code "29") (name "/RS485A") (class "Default")
      (node (ref "E5") (pin "1") (pinfunction "1_1") (pintype "passive"))
      (node (ref "R25") (pin "2") (pinfunction "2_2") (pintype "passive"))
      (node (ref "U7") (pin "6") (pinfunction "A_6") (pintype "bidirectional"))
      (node (ref "X6") (pin "2") (pinfunction "2_2") (pintype "passive"))
    )
    (net (code "30") (name "/RS485B") (class "Default")
      (node (ref "E4") (pin "1") (pinfunction "1_1") (pintype "passive"))
      (node (ref "J3") (pin "1") (pinfunction "1_1") (pintype "passive"))
      (node (ref "U7") (pin "7") (pinfunction "B_7") (pintype "bidirectional"))
      (node (ref "X6") (pin "1") (pinfunction "1_1") (pintype "passive"))
    )
    (net (code "31") (name "/RS485_DE") (class "Default")
      (node (ref "U7") (pin "3") (pinfunction "DE_3") (pintype "input"))
    )
    (net (code "32") (name "/RS485_RX") (class "Default")
      (node (ref "U7") (pin "1") (pinfunction "RO_1") (pintype "output"))
    )
    (net (code "33") (name "/RS485_TX") (class "Default")
      (node (ref "U7") (pin "4") (pinfunction "DI_4") (pintype "input"))
    )
    (net (code "34") (name "/S5_RESET") (class "Default")
      (node (ref "C2") (pin "1") (pinfunction "1_1") (pintype "passive"))
      (node (ref "R3") (pin "1") (pinfunction "1_1") (pintype "passive"))
      (node (ref "U1") (pin "38") (pinfunction "RES_38") (pintype "input"))
    )
    (net (code "35") (name "/SD_CLK") (class "Default")
      (node (ref "uSD1") (pin "5") (pinfunction "CLK/SCLK_5") (pintype "passive"))
    )
    (net (code "36") (name "/SD_CMD") (class "Default")
      (node (ref "uSD1") (pin "3") (pinfunction "CMD/DI_3") (pintype "passive"))
    )
    (net (code "37") (name "/SD_DAT0") (class "Default")
      (node (ref "uSD1") (pin "7") (pinfunction "DAT0/DO_7") (pintype "passive"))
    )
    (net (code "38") (name "/SD_DAT1") (class "Default")
      (node (ref "uSD1") (pin "8") (pinfunction "DAT1_8") (pintype "passive"))
    )
    (net (code "39") (name "/SD_DAT2") (class "Default")
      (node (ref "uSD1") (pin "1") (pinfunction "DAT2_1") (pintype "passive"))
    )
    (net (code "40") (name "/SD_DAT3") (class "Default")
      (node (ref "uSD1") (pin "2") (pinfunction "CD/DAT3/CS_2") (pintype "passive"))
    )
    (net (code "41") (name "/SOUND") (class "Default")
      (node (ref "C20") (pin "1") (pinfunction "1_1") (pintype "passive"))
    )
    (net (code "42") (name "/USBHS_N") (class "Default")
      (node (ref "U1") (pin "27") (pinfunction "USBFS0_DM_27") (pintype "bidirectional"))
      (node (ref "U2") (pin "6") (pinfunction "6_6") (pintype "passive"))
      (node (ref "X3") (pin "A7") (pinfunction "Dn1_A7") (pintype "passive"))
      (node (ref "X3") (pin "B7") (pinfunction "Dn2_B7") (pintype "passive"))
    )
    (net (code "43") (name "/USBHS_P") (class "Default")
      (node (ref "U1") (pin "28") (pinfunction "USBFS0_DP_28") (pintype "bidirectional"))
      (node (ref "U2") (pin "5") (pinfunction "5_5") (pintype "passive"))
      (node (ref "X3") (pin "A6") (pinfunction "Dp1_A6") (pintype "passive"))
      (node (ref "X3") (pin "B6") (pinfunction "Dp2_B6") (pintype "passive"))
    )
    (net (code "44") (name "/USBHS_STATE") (class "Default")
      (node (ref "C4") (pin "2") (pinfunction "2_2") (pintype "passive"))
      (node (ref "R7") (pin "1") (pinfunction "1_1") (pintype "passive"))
      (node (ref "R9") (pin "2") (pinfunction "2_2") (pintype "passive"))
    )
    (net (code "45") (name "GND") (class "Default")
      (node (ref "BAT1") (pin "1") (pinfunction "1_1") (pintype "passive"))
      (node (ref "C1") (pin "2") (pinfunction "2_2") (pintype "passive"))
      (node (ref "C10") (pin "1") (pinfunction "1_1") (pintype "passive"))
      (node (ref "C11") (pin "2") (pinfunction "2_2") (pintype "passive"))
      (node (ref "C12") (pin "2") (pinfunction "2_2") (pintype "passive"))
      (node (ref "C13") (pin "2") (pinfunction "2_2") (pintype "passive"))
      (node (ref "C14") (pin "2") (pinfunction "2_2") (pintype "passive"))
      (node (ref "C15") (pin "1") (pinfunction "1_1") (pintype "passive"))
      (node (ref "C16") (pin "1") (pinfunction "1_1") (pintype "passive"))
      (node (ref "C17") (pin "1") (pinfunction "1_1") (pintype "passive"))
      (node (ref "C18") (pin "1") (pinfunction "1_1") (pintype "passive"))
      (node (ref "C19") (pin "2") (pinfunction "2_2") (pintype "passive"))
      (node (ref "C2") (pin "2") (pinfunction "2_2") (pintype "passive"))
      (node (ref "C21") (pin "2") (pinfunction "2_2") (pintype "passive"))
      (node (ref "C22") (pin "2") (pinfunction "2_2") (pintype "passive"))
      (node (ref "C23") (pin "1") (pinfunction "1_1") (pintype "passive"))
      (node (ref "C24") (pin "1") (pinfunction "1_1") (pintype "passive"))
      (node (ref "C25") (pin "2") (pinfunction "2_2") (pintype "passive"))
      (node (ref "C26") (pin "1") (pinfunction "1_1") (pintype "passive"))
      (node (ref "C27") (pin "2") (pinfunction "2_2") (pintype "passive"))
      (node (ref "C28") (pin "1") (pinfunction "1_1") (pintype "passive"))
      (node (ref "C29") (pin "1") (pinfunction "1_1") (pintype "passive"))
      (node (ref "C3") (pin "1") (pinfunction "1_1") (pintype "passive"))
      (node (ref "C4") (pin "1") (pinfunction "1_1") (pintype "passive"))
      (node (ref "C5") (pin "1") (pinfunction "1_1") (pintype "passive"))
      (node (ref "C6") (pin "2") (pinfunction "2_2") (pintype "passive"))
      (node (ref "C7") (pin "2") (pinfunction "2_2") (pintype "passive"))
      (node (ref "C8") (pin "2") (pinfunction "2_2") (pintype "passive"))
      (node (ref "C9") (pin "1") (pinfunction "1_1") (pintype "passive"))
      (node (ref "E1") (pin "1") (pinfunction "1_1") (pintype "passive"))
      (node (ref "E2") (pin "1") (pinfunction "1_1") (pintype "passive"))
      (node (ref "E3") (pin "1") (pinfunction "1_1") (pintype "passive"))
      (node (ref "E4") (pin "2") (pinfunction "2_2") (pintype "passive"))
      (node (ref "E5") (pin "2") (pinfunction "2_2") (pintype "passive"))
      (node (ref "E6") (pin "1") (pinfunction "1_1") (pintype "passive"))
      (node (ref "R11") (pin "1") (pinfunction "1_1") (pintype "passive"))
      (node (ref "R12") (pin "1") (pinfunction "1_1") (pintype "passive"))
      (node (ref "R16") (pin "2") (pinfunction "2_2") (pintype "passive"))
      (node (ref "R17") (pin "2") (pinfunction "2_2") (pintype "passive"))
      (node (ref "R9") (pin "1") (pinfunction "1_1") (pintype "passive"))
      (node (ref "SW1") (pin "1") (pinfunction "1_1") (pintype "passive"))
      (node (ref "U1") (pin "12") (pinfunction "VSS_12") (pintype "power_in"))
      (node (ref "U1") (pin "26") (pinfunction "USBFS0_VSS_26") (pintype "power_in"))
      (node (ref "U1") (pin "45") (pinfunction "VSS_45") (pintype "power_in"))
      (node (ref "U1") (pin "63") (pinfunction "VSS_63") (pintype "power_in"))
      (node (ref "U1") (pin "83") (pinfunction "VSS_83") (pintype "power_in"))
      (node (ref "U1") (pin "86") (pinfunction "VREFL_86") (pintype "power_in"))
      (node (ref "U1") (pin "89") (pinfunction "AVSS0_89") (pintype "power_in"))
      (node (ref "U1") (pin "90") (pinfunction "VREFL0_90") (pintype "power_in"))
      (node (ref "U2") (pin "2") (pinfunction "2_2") (pintype "passive"))
      (node (ref "U2") (pin "3") (pinfunction "3_3") (pintype "passive"))
      (node (ref "U2") (pin "4") (pinfunction "4_4") (pintype "passive"))
      (node (ref "U2") (pin "7") (pinfunction "7_7") (pintype "passive"))
      (node (ref "U3") (pin "2") (pinfunction "GND_2") (pintype "power_in"))
      (node (ref "U3") (pin "9") (pinfunction "WAKE_9") (pintype "input"))
      (node (ref "U4") (pin "1") (pinfunction "STDBY_1") (pintype "passive"))
      (node (ref "U4") (pin "7") (pinfunction "GND_7") (pintype "passive"))
      (node (ref "U5") (pin "3") (pinfunction "GND_3") (pintype "power_in"))
      (node (ref "U6") (pin "3") (pinfunction "GND_3") (pintype "power_in"))
      (node (ref "U7") (pin "2") (pinfunction "~{RE}_2") (pintype "input"))
      (node (ref "U7") (pin "5") (pinfunction "GND_5") (pintype "power_in"))
      (node (ref "VD1") (pin "2") (pinfunction "2_2") (pintype "passive"))
      (node (ref "VD2") (pin "2") (pinfunction "2_2") (pintype "passive"))
      (node (ref "VD3") (pin "2") (pinfunction "2_2") (pintype "passive"))
      (node (ref "X11") (pin "1") (pinfunction "GND_1") (pintype "passive"))
      (node (ref "X2") (pin "3") (pinfunction "3_3") (pintype "passive"))
      (node (ref "X2") (pin "5") (pinfunction "5_5") (pintype "passive"))
      (node (ref "X2") (pin "8") (pinfunction "8_8") (pintype "passive"))
      (node (ref "X3") (pin "A1") (pinfunction "GND_A1") (pintype "passive"))
      (node (ref "X3") (pin "A12") (pinfunction "GND_A12") (pintype "passive"))
      (node (ref "X3") (pin "B1") (pinfunction "GND_B1") (pintype "passive"))
      (node (ref "X3") (pin "B12") (pinfunction "GND_B12") (pintype "passive"))
      (node (ref "X3") (pin "Shell") (pinfunction "Shield_Shell") (pintype "passive"))
      (node (ref "Z1") (pin "2") (pinfunction "2_2") (pintype "passive"))
      (node (ref "Z1") (pin "4") (pinfunction "4_4") (pintype "passive"))
      (node (ref "uSD1") (pin "10") (pinfunction "WP_10") (pintype "passive"))
      (node (ref "uSD1") (pin "11") (pinfunction "GND_11") (pintype "passive"))
      (node (ref "uSD1") (pin "12") (pinfunction "GND_12") (pintype "passive"))
      (node (ref "uSD1") (pin "6") (pinfunction "VSS2_6") (pintype "passive"))
      (node (ref "uSD1") (pin "9") (pintype "passive"))
    )
    (net (code "46") (name "Net-(C20-Pad2)") (class "Default")
      (node (ref "C20") (pin "2") (pinfunction "2_2") (pintype "passive"))
      (node (ref "R19") (pin "1") (pinfunction "1_1") (pintype "passive"))
    )
    (net (code "47") (name "Net-(C21-Pad1)") (class "Default")
      (node (ref "C21") (pin "1") (pinfunction "1_1") (pintype "passive"))
      (node (ref "E3") (pin "2") (pinfunction "2_2") (pintype "passive"))
      (node (ref "X4") (pin "3") (pinfunction "3_3") (pintype "passive"))
    )
    (net (code "48") (name "Net-(C27-Pad1)") (class "Default")
      (node (ref "C27") (pin "1") (pinfunction "1_1") (pintype "passive"))
      (node (ref "E6") (pin "2") (pinfunction "2_2") (pintype "passive"))
      (node (ref "X6") (pin "3") (pinfunction "3_3") (pintype "passive"))
    )
    (net (code "49") (name "Net-(J1-Pad2)") (class "Default")
      (node (ref "J1") (pin "2") (pinfunction "2_2") (pintype "passive"))
      (node (ref "R15") (pin "1") (pinfunction "1_1") (pintype "passive"))
    )
    (net (code "50") (name "Net-(J2-Pad1)") (class "Default")
      (node (ref "J2") (pin "1") (pinfunction "1_1") (pintype "passive"))
      (node (ref "R23") (pin "2") (pinfunction "2_2") (pintype "passive"))
    )
    (net (code "51") (name "Net-(J3-Pad2)") (class "Default")
      (node (ref "J3") (pin "2") (pinfunction "2_2") (pintype "passive"))
      (node (ref "R25") (pin "1") (pinfunction "1_1") (pintype "passive"))
    )
    (net (code "52") (name "Net-(LED1-Pad1)") (class "Default")
      (node (ref "LED1") (pin "1") (pinfunction "1_1") (pintype "passive"))
      (node (ref "R14") (pin "1") (pinfunction "1_1") (pintype "passive"))
    )
    (net (code "53") (name "Net-(LED2-Pad1)") (class "Default")
      (node (ref "LED2") (pin "1") (pinfunction "1_1") (pintype "passive"))
      (node (ref "R24") (pin "1") (pinfunction "1_1") (pintype "passive"))
    )
    (net (code "54") (name "Net-(R5-Pad1)") (class "Default")
      (node (ref "R5") (pin "1") (pinfunction "1_1") (pintype "passive"))
      (node (ref "R8") (pin "1") (pinfunction "1_1") (pintype "passive"))
      (node (ref "VD2") (pin "1") (pinfunction "1_1") (pintype "passive"))
      (node (ref "X2") (pin "4") (pinfunction "4_4") (pintype "passive"))
    )
    (net (code "55") (name "Net-(R6-Pad1)") (class "Default")
      (node (ref "R6") (pin "1") (pinfunction "1_1") (pintype "passive"))
      (node (ref "VD3") (pin "1") (pinfunction "1_1") (pintype "passive"))
      (node (ref "X2") (pin "2") (pinfunction "2_2") (pintype "passive"))
    )
    (net (code "56") (name "Net-(R10-Pad1)") (class "Default")
      (node (ref "R10") (pin "1") (pinfunction "1_1") (pintype "passive"))
      (node (ref "R4") (pin "1") (pinfunction "1_1") (pintype "passive"))
      (node (ref "VD1") (pin "1") (pinfunction "1_1") (pintype "passive"))
      (node (ref "X2") (pin "7") (pinfunction "7_7") (pintype "passive"))
    )
    (net (code "57") (name "Net-(R21-Pad2)") (class "Default")
      (node (ref "R21") (pin "2") (pinfunction "2_2") (pintype "passive"))
      (node (ref "SW1") (pin "2") (pinfunction "2_2") (pintype "passive"))
    )
    (net (code "58") (name "Net-(R22-Pad2)") (class "Default")
      (node (ref "R22") (pin "2") (pinfunction "2_2") (pintype "passive"))
      (node (ref "SW1") (pin "3") (pinfunction "3_3") (pintype "passive"))
    )
    (net (code "59") (name "Net-(U1B-AVCC0)") (class "Default")
      (node (ref "C13") (pin "1") (pinfunction "1_1") (pintype "passive"))
      (node (ref "L1") (pin "2") (pinfunction "2_2") (pintype "passive"))
      (node (ref "U1") (pin "87") (pinfunction "VREFH_87") (pintype "power_in"))
      (node (ref "U1") (pin "88") (pinfunction "AVCC0_88") (pintype "power_in"))
      (node (ref "U1") (pin "91") (pinfunction "VREFH0_91") (pintype "power_in"))
    )
    (net (code "60") (name "Net-(U1B-CGC0_XCIN)") (class "Default")
      (node (ref "C9") (pin "2") (pinfunction "2_2") (pintype "passive"))
      (node (ref "U1") (pin "10") (pinfunction "CGC0_XCIN_10") (pintype "input"))
      (node (ref "Z2") (pin "1") (pinfunction "1_1") (pintype "passive"))
    )
    (net (code "61") (name "Net-(U1B-CGC0_XCOUT)") (class "Default")
      (node (ref "C10") (pin "2") (pinfunction "2_2") (pintype "passive"))
      (node (ref "U1") (pin "11") (pinfunction "CGC0_XCOUT_11") (pintype "output"))
      (node (ref "Z2") (pin "2") (pinfunction "2_2") (pintype "passive"))
    )
    (net (code "62") (name "Net-(U1B-P200{slash}ICU0_NMI)") (class "Default")
      (node (ref "R2") (pin "1") (pinfunction "1_1") (pintype "passive"))
      (node (ref "U1") (pin "40") (pinfunction "P200/ICU0_NMI_40") (pintype "bidirectional"))
    )
    (net (code "63") (name "Net-(U1B-P201{slash}SYSTEM0_MD)") (class "Default")
      (node (ref "R1") (pin "1") (pinfunction "1_1") (pintype "passive"))
      (node (ref "U1") (pin "39") (pinfunction "P201/SYSTEM0_MD_39") (pintype "bidirectional"))
    )
    (net (code "64") (name "Net-(U1B-P212{slash}EXTAL)") (class "Default")
      (node (ref "C5") (pin "2") (pinfunction "2_2") (pintype "passive"))
      (node (ref "U1") (pin "14") (pinfunction "P212/EXTAL_14") (pintype "bidirectional"))
      (node (ref "Z1") (pin "3") (pinfunction "3_3") (pintype "passive"))
    )
    (net (code "65") (name "Net-(U1B-P213{slash}XTAL)") (class "Default")
      (node (ref "C3") (pin "2") (pinfunction "2_2") (pintype "passive"))
      (node (ref "U1") (pin "13") (pinfunction "P213/XTAL_13") (pintype "bidirectional"))
      (node (ref "Z1") (pin "1") (pinfunction "1_1") (pintype "passive"))
    )
    (net (code "66") (name "Net-(U1B-VBATT)") (class "Default")
      (node (ref "BAT1") (pin "2") (pinfunction "2_2") (pintype "passive"))
      (node (ref "R13") (pin "2") (pinfunction "2_2") (pintype "passive"))
      (node (ref "U1") (pin "8") (pinfunction "VBATT_8") (pintype "power_in"))
    )
    (net (code "67") (name "Net-(U1B-VCL)") (class "Default")
      (node (ref "C11") (pin "1") (pinfunction "1_1") (pintype "passive"))
      (node (ref "U1") (pin "64") (pinfunction "VCL_64") (pintype "power_in"))
    )
    (net (code "68") (name "Net-(U1B-VCL0)") (class "Default")
      (node (ref "C12") (pin "1") (pinfunction "1_1") (pintype "passive"))
      (node (ref "U1") (pin "9") (pinfunction "VCL0_9") (pintype "power_in"))
    )
    (net (code "69") (name "Net-(U3-SPLIT)") (class "Default")
      (node (ref "C24") (pin "2") (pinfunction "2_2") (pintype "passive"))
      (node (ref "R15") (pin "2") (pinfunction "2_2") (pintype "passive"))
      (node (ref "R23") (pin "1") (pinfunction "1_1") (pintype "passive"))
      (node (ref "U3") (pin "11") (pinfunction "SPLIT_11") (pintype "passive"))
    )
    (net (code "70") (name "Net-(U4-BYPASS)") (class "Default")
      (node (ref "C19") (pin "1") (pinfunction "1_1") (pintype "passive"))
      (node (ref "U4") (pin "2") (pinfunction "BYPASS_2") (pintype "passive"))
      (node (ref "U4") (pin "3") (pinfunction "VIN+_3") (pintype "passive"))
    )
    (net (code "71") (name "Net-(U4-OUT+)") (class "Default")
      (node (ref "U4") (pin "8") (pinfunction "OUT+_8") (pintype "passive"))
      (node (ref "X5") (pin "1") (pinfunction "1_1") (pintype "passive"))
    )
    (net (code "72") (name "Net-(U4-OUT-)") (class "Default")
      (node (ref "R20") (pin "2") (pinfunction "2_2") (pintype "passive"))
      (node (ref "U4") (pin "5") (pinfunction "OUT-_5") (pintype "passive"))
      (node (ref "X5") (pin "2") (pinfunction "2_2") (pintype "passive"))
    )
    (net (code "73") (name "Net-(U4-VIN-)") (class "Default")
      (node (ref "R19") (pin "2") (pinfunction "2_2") (pintype "passive"))
      (node (ref "R20") (pin "1") (pinfunction "1_1") (pintype "passive"))
      (node (ref "U4") (pin "4") (pinfunction "VIN-_4") (pintype "passive"))
    )
    (net (code "74") (name "Net-(U5-Y)") (class "Default")
      (node (ref "R21") (pin "1") (pinfunction "1_1") (pintype "passive"))
      (node (ref "U5") (pin "4") (pinfunction "Y_4") (pintype "open_collector"))
    )
    (net (code "75") (name "Net-(U6-Y)") (class "Default")
      (node (ref "R22") (pin "1") (pinfunction "1_1") (pintype "passive"))
      (node (ref "U6") (pin "4") (pinfunction "Y_4") (pintype "open_collector"))
    )
    (net (code "76") (name "Net-(VD4-C)") (class "Default")
      (node (ref "R13") (pin "1") (pinfunction "1_1") (pintype "passive"))
      (node (ref "VD4") (pin "1") (pinfunction "C_1") (pintype "passive"))
    )
    (net (code "77") (name "Net-(X3-CC)") (class "Default")
      (node (ref "R12") (pin "2") (pinfunction "2_2") (pintype "passive"))
      (node (ref "X3") (pin "A5") (pinfunction "CC_A5") (pintype "passive"))
    )
    (net (code "78") (name "Net-(X3-VCONN)") (class "Default")
      (node (ref "R11") (pin "2") (pinfunction "2_2") (pintype "passive"))
      (node (ref "X3") (pin "B5") (pinfunction "VCONN_B5") (pintype "passive"))
    )
    (net (code "79") (name "unconnected-(U3-ERR_N-Pad8)") (class "Default")
      (node (ref "U3") (pin "8") (pinfunction "ERR_N_8") (pintype "bidirectional"))
    )
    (net (code "80") (name "unconnected-(U3-INH-Pad7)") (class "Default")
      (node (ref "U3") (pin "7") (pinfunction "INH_7") (pintype "bidirectional"))
    )
    (net (code "81") (name "unconnected-(X3-SBU1-PadA8)") (class "Default")
      (node (ref "X3") (pin "A8") (pinfunction "SBU1_A8") (pintype "passive"))
    )
    (net (code "82") (name "unconnected-(X3-SBU2-PadB8)") (class "Default")
      (node (ref "X3") (pin "B8") (pinfunction "SBU2_B8") (pintype "passive"))
    )
    (net (code "83") (name "unconnected-(X3-SSRXn1-PadB10)") (class "Default")
      (node (ref "X3") (pin "B10") (pinfunction "SSRXn1_B10") (pintype "passive"))
    )
    (net (code "84") (name "unconnected-(X3-SSRXn2-PadA10)") (class "Default")
      (node (ref "X3") (pin "A10") (pinfunction "SSRXn2_A10") (pintype "passive"))
    )
    (net (code "85") (name "unconnected-(X3-SSRXp1-PadB11)") (class "Default")
      (node (ref "X3") (pin "B11") (pinfunction "SSRXp1_B11") (pintype "passive"))
    )
    (net (code "86") (name "unconnected-(X3-SSRXp2-PadA11)") (class "Default")
      (node (ref "X3") (pin "A11") (pinfunction "SSRXp2_A11") (pintype "passive"))
    )
    (net (code "87") (name "unconnected-(X3-SSTXn1-PadA3)") (class "Default")
      (node (ref "X3") (pin "A3") (pinfunction "SSTXn1_A3") (pintype "passive"))
    )
    (net (code "88") (name "unconnected-(X3-SSTXn2-PadB3)") (class "Default")
      (node (ref "X3") (pin "B3") (pinfunction "SSTXn2_B3") (pintype "passive"))
    )
    (net (code "89") (name "unconnected-(X3-SSTXp1-PadA2)") (class "Default")
      (node (ref "X3") (pin "A2") (pinfunction "SSTXp1_A2") (pintype "passive"))
    )
    (net (code "90") (name "unconnected-(X3-SSTXp2-PadB2)") (class "Default")
      (node (ref "X3") (pin "B2") (pinfunction "SSTXp2_B2") (pintype "passive"))
    )
  )
)
